# 555flasher.net
KiCad netlist of a schematic drawn in EAGLE
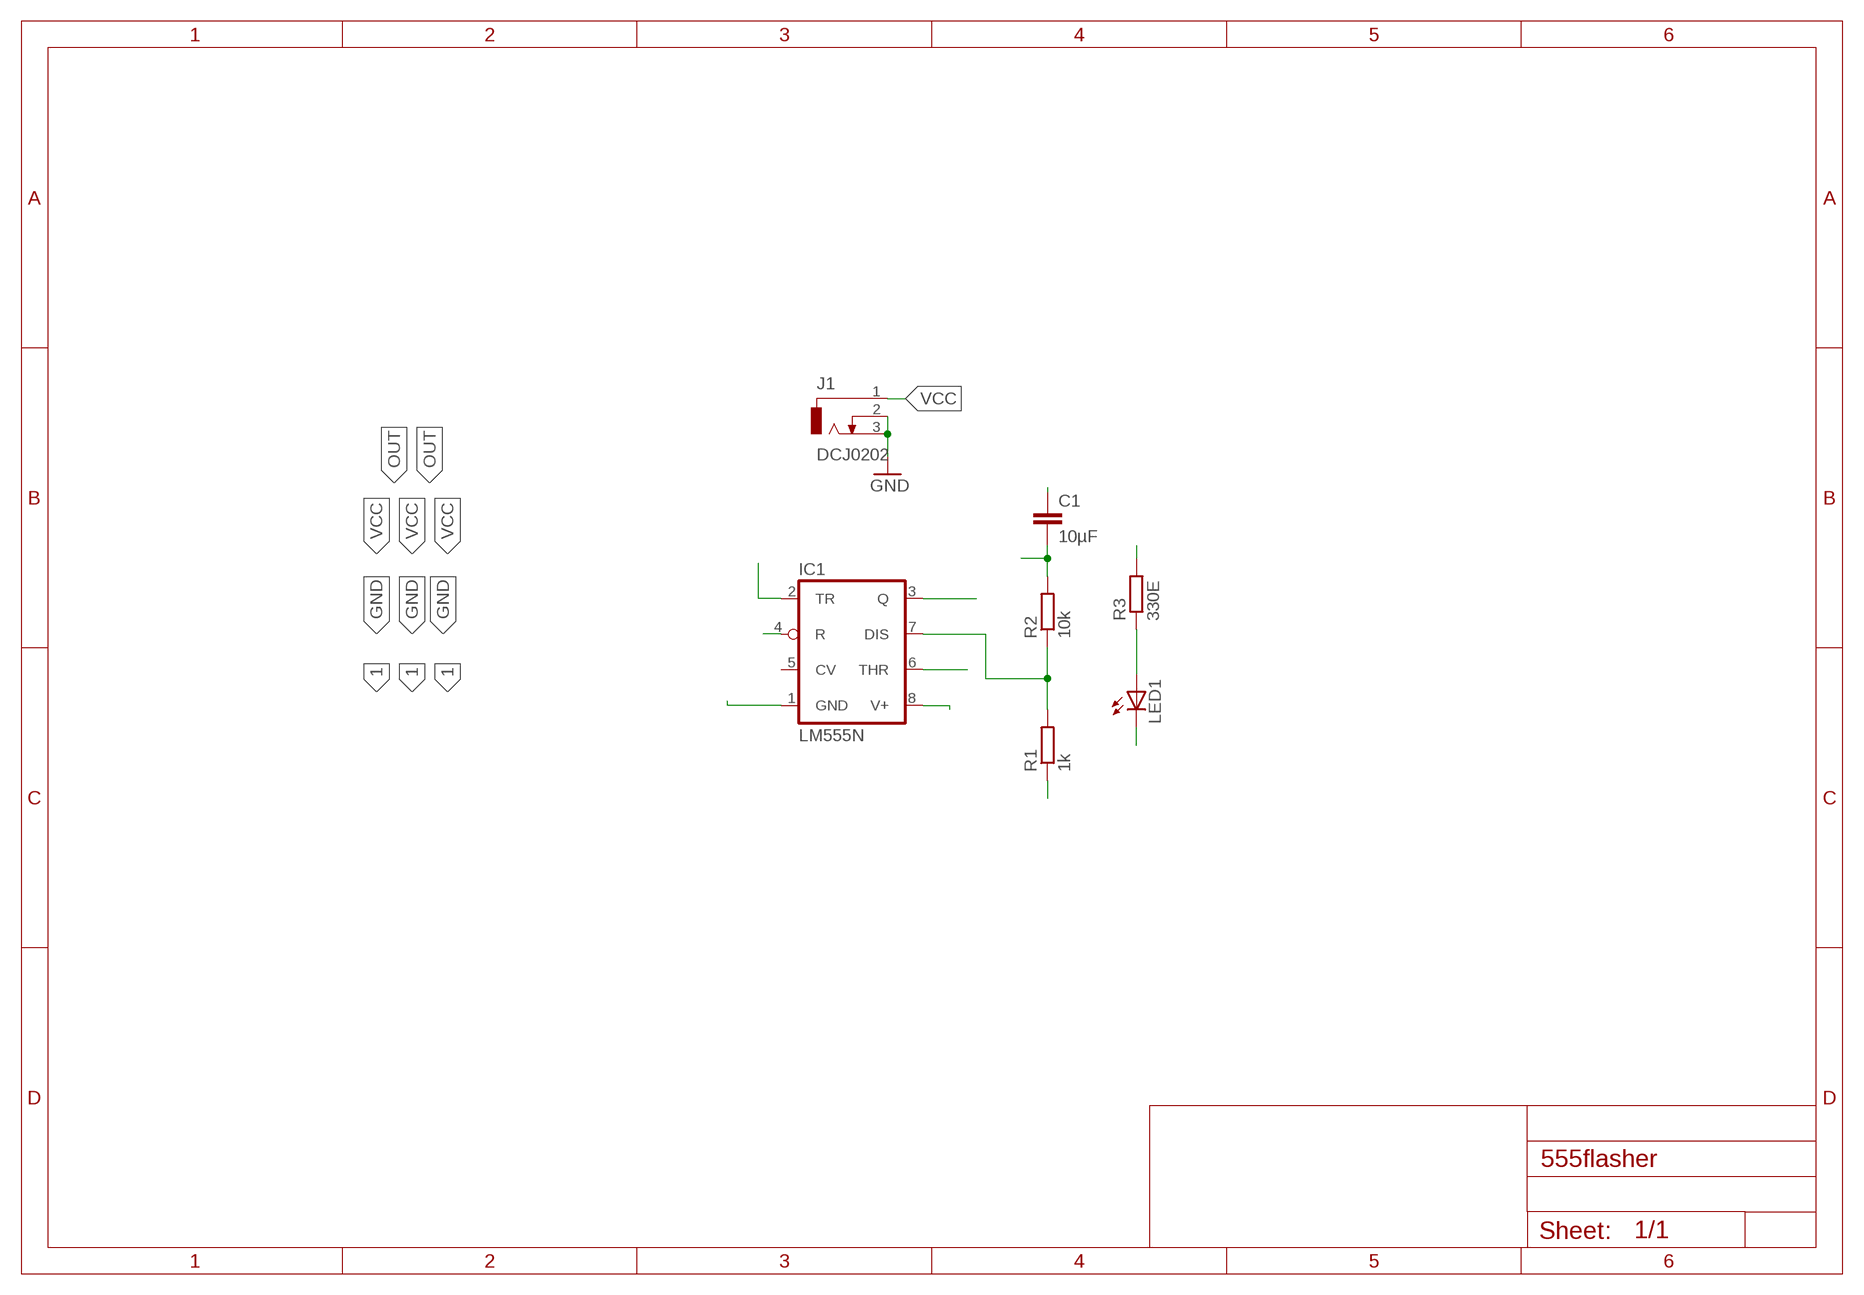
[diagram p0: schematic, sheet 1]

(export (version "E")
  (design (tool "Eeschema 10.0.6"))
  (components
    (comp (ref "C1")
      (value "10µF")
      (footprint "eagle-import:C025-025X050")
      (libsource (lib "eagle-import") (part "C-EU025-025X050"))
    )
    (comp (ref "IC1")
      (value "LM555N")
      (footprint "eagle-import:DIL08")
      (libsource (lib "eagle-import") (part "555NLM"))
    )
    (comp (ref "J1")
      (value "DCJ0202")
      (footprint "eagle-import:DCJ0202")
      (libsource (lib "eagle-import") (part "DCJ0202"))
    )
    (comp (ref "LED1")
      (value "LED5MM")
      (footprint "eagle-import:LED5MM")
      (libsource (lib "eagle-import") (part "LED5MM"))
    )
    (comp (ref "R1")
      (value "1k")
      (footprint "eagle-import:0207_10")
      (libsource (lib "eagle-import") (part "R-EU_0207/10"))
    )
    (comp (ref "R2")
      (value "10k")
      (footprint "eagle-import:0207_10")
      (libsource (lib "eagle-import") (part "R-EU_0207/10"))
    )
    (comp (ref "R3")
      (value "330E")
      (footprint "eagle-import:0207_10")
      (libsource (lib "eagle-import") (part "R-EU_0207/10"))
    )
  )
  (nets
    (net (code "1") (name "1") (class "Default")
      (node (ref "C1") (pin "2") (pinfunction "2_2") (pintype "passive"))
      (node (ref "IC1") (pin "2") (pinfunction "TR_2") (pintype "input"))
      (node (ref "IC1") (pin "6") (pinfunction "THR_6") (pintype "input"))
      (node (ref "R2") (pin "2") (pinfunction "2_2") (pintype "passive"))
    )
    (net (code "2") (name "GND") (class "Default")
      (node (ref "C1") (pin "1") (pinfunction "1_1") (pintype "passive"))
      (node (ref "IC1") (pin "1") (pinfunction "GND_1") (pintype "power_in"))
      (node (ref "J1") (pin "2") (pinfunction "2_2") (pintype "passive"))
      (node (ref "J1") (pin "3") (pinfunction "3_3") (pintype "passive"))
      (node (ref "LED1") (pin "K") (pinfunction "C_K") (pintype "passive"))
    )
    (net (code "3") (name "Net-(IC1-DIS)") (class "Default")
      (node (ref "IC1") (pin "7") (pinfunction "DIS_7") (pintype "input"))
      (node (ref "R1") (pin "2") (pinfunction "2_2") (pintype "passive"))
      (node (ref "R2") (pin "1") (pinfunction "1_1") (pintype "passive"))
    )
    (net (code "4") (name "Net-(LED1-PadA)") (class "Default")
      (node (ref "LED1") (pin "A") (pinfunction "A_A") (pintype "passive"))
      (node (ref "R3") (pin "1") (pinfunction "1_1") (pintype "passive"))
    )
    (net (code "5") (name "OUT") (class "Default")
      (node (ref "IC1") (pin "3") (pinfunction "Q_3") (pintype "output"))
      (node (ref "R3") (pin "2") (pinfunction "2_2") (pintype "passive"))
    )
    (net (code "6") (name "VCC") (class "Default")
      (node (ref "IC1") (pin "4") (pinfunction "R_4") (pintype "input"))
      (node (ref "IC1") (pin "8") (pinfunction "V+_8") (pintype "power_in"))
      (node (ref "J1") (pin "1") (pinfunction "1_1") (pintype "passive"))
      (node (ref "R1") (pin "1") (pinfunction "1_1") (pintype "passive"))
    )
    (net (code "7") (name "unconnected-(IC1-CV-Pad5)") (class "Default")
      (node (ref "IC1") (pin "5") (pinfunction "CV_5") (pintype "input"))
    )
  )
)
